# Revolution.net
KiCad netlist of a schematic drawn in Altium Designer
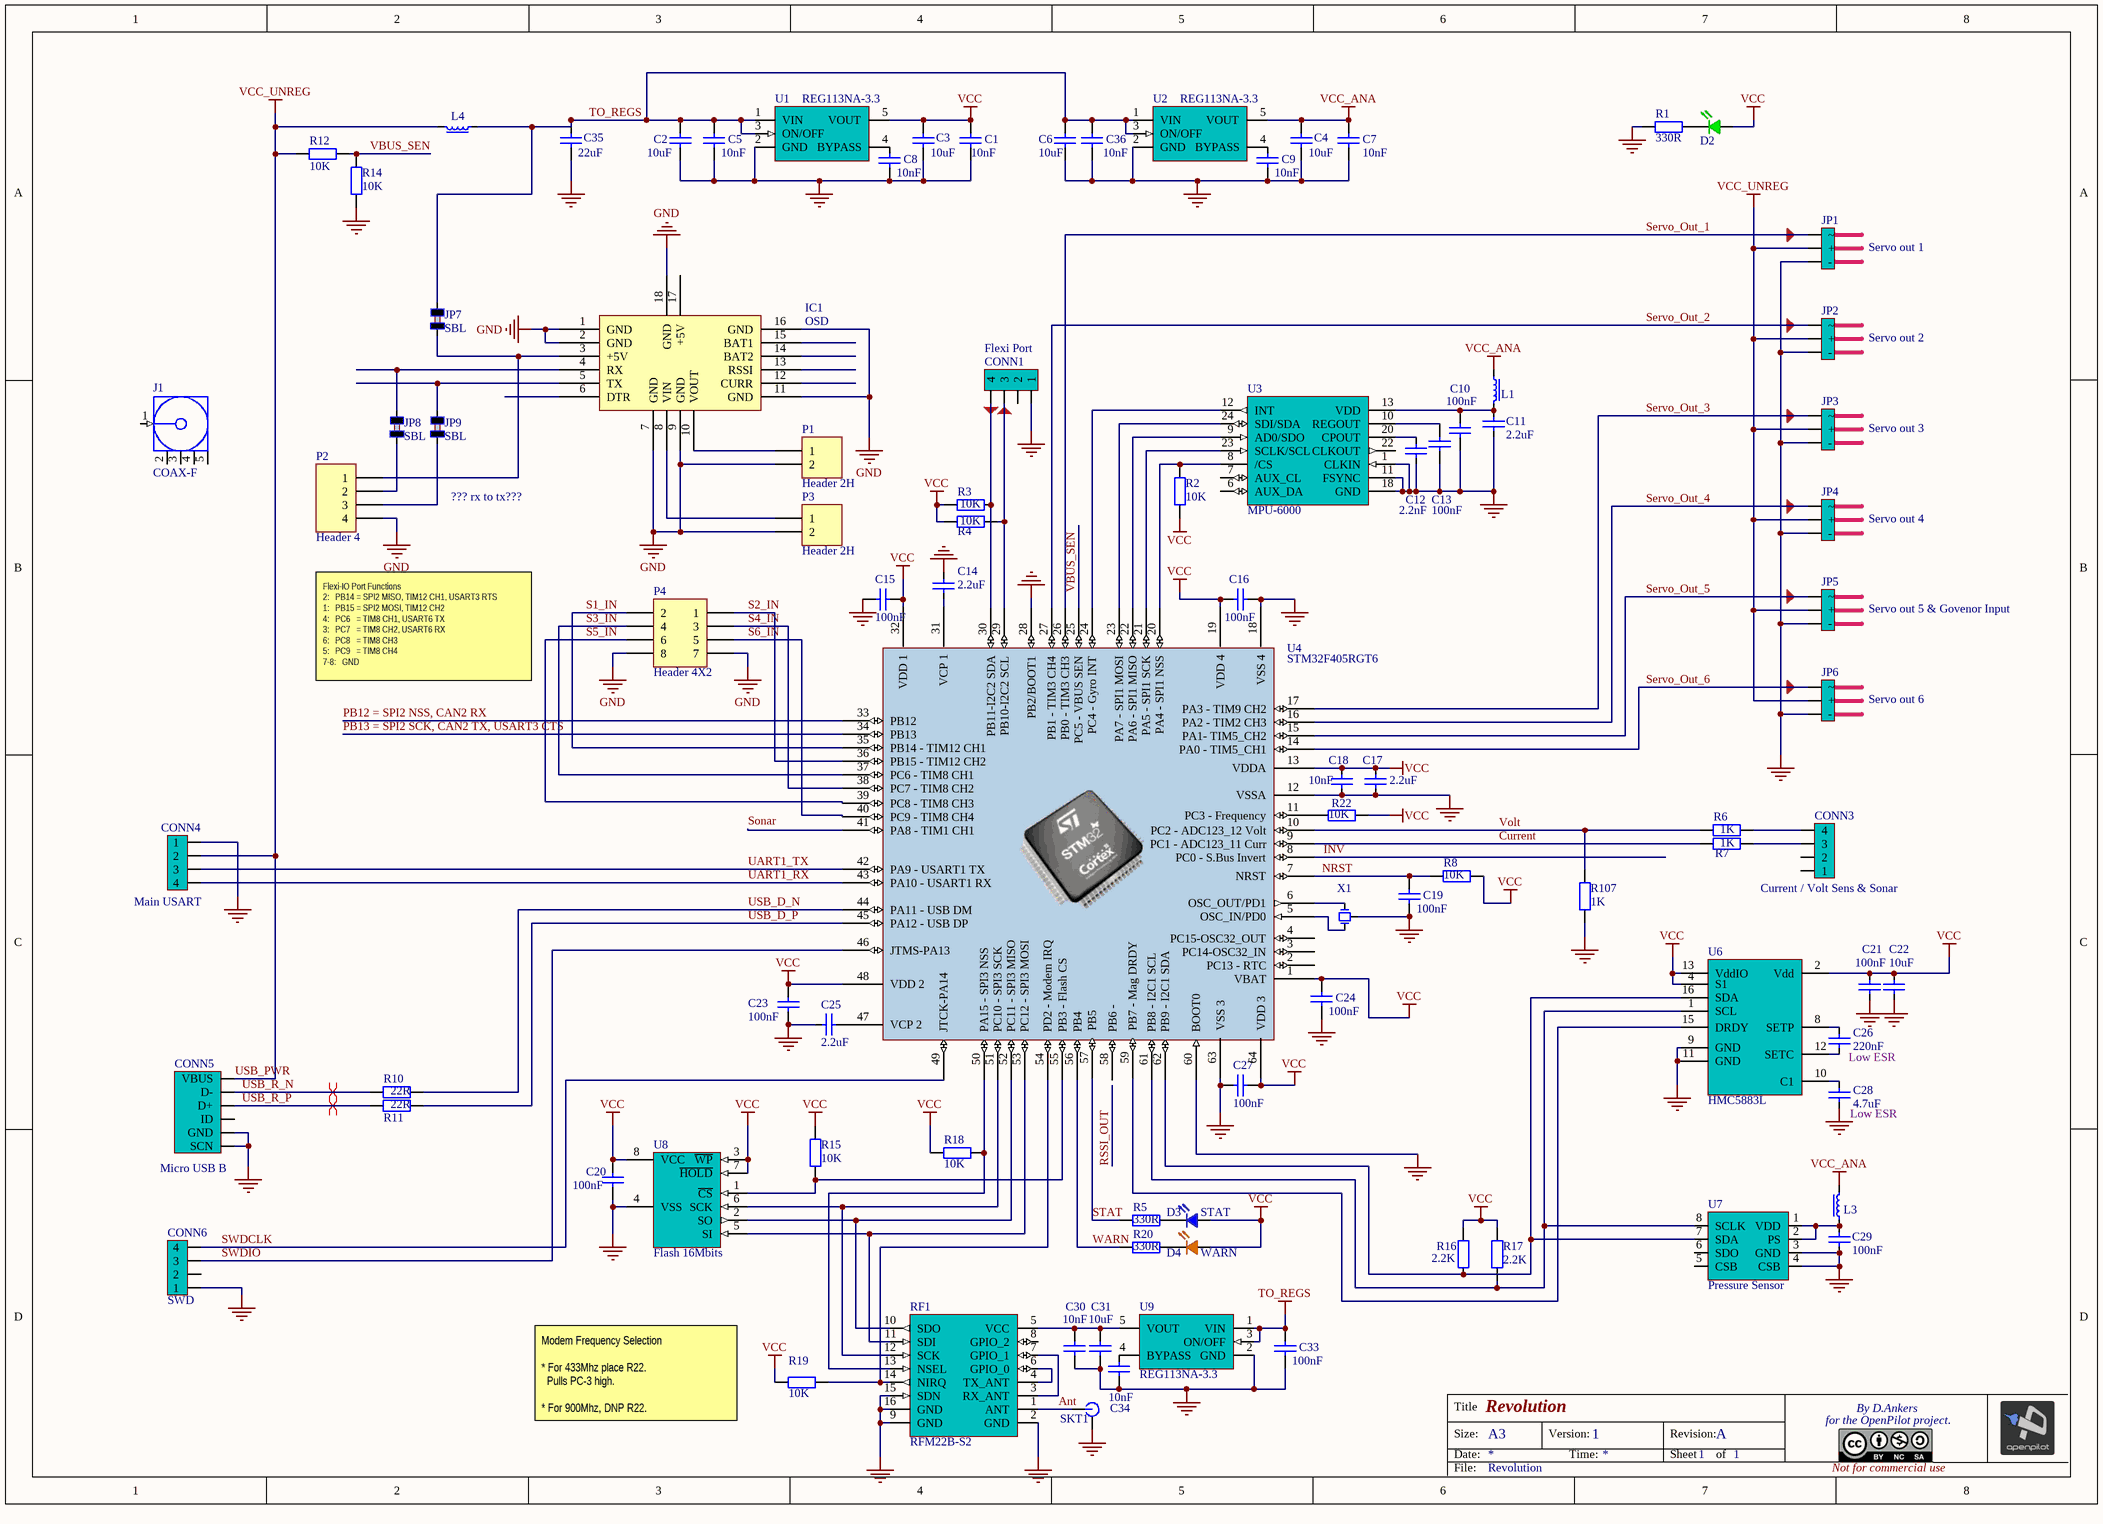
[diagram p0: Revolution.SchDoc]

(export (version "E")
  (design (tool "Eeschema 10.0.6"))
  (components
    (comp (ref "C1")
      (value "10nF")
      (footprint "CAP402N")
      (description "Capacitor SMD")
      (fields (field (name "Comment") "10n") (field (name "PUBLISHER") "The OpenPilot Project"))
      (libsource (lib "OpenPilot") (part "Cap402"))
    )
    (comp (ref "C2")
      (value "10uF")
      (footprint "CAP805L")
      (description "Capacitor SMD")
      (fields (field (name "Comment") "Cap805") (field (name "PUBLISHER") "The OpenPilot Project"))
      (libsource (lib "OpenPilot") (part "Cap805"))
    )
    (comp (ref "C3")
      (value "10uF")
      (footprint "CAP805L")
      (description "Capacitor SMD")
      (fields (field (name "Comment") "Cap805") (field (name "PUBLISHER") "The OpenPilot Project"))
      (libsource (lib "OpenPilot") (part "Cap805"))
    )
    (comp (ref "C4")
      (value "10uF")
      (footprint "CAP805L")
      (description "Capacitor SMD")
      (fields (field (name "Comment") "Cap805") (field (name "PUBLISHER") "The OpenPilot Project"))
      (libsource (lib "OpenPilot") (part "Cap805"))
    )
    (comp (ref "C5")
      (value "10nF")
      (footprint "CAP402N")
      (description "Capacitor SMD")
      (fields (field (name "Comment") "10n") (field (name "PUBLISHER") "The OpenPilot Project"))
      (libsource (lib "OpenPilot") (part "Cap402"))
    )
    (comp (ref "C6")
      (value "10uF")
      (footprint "CAP805L")
      (description "Capacitor SMD")
      (fields (field (name "Comment") "Cap805") (field (name "PUBLISHER") "The OpenPilot Project"))
      (libsource (lib "OpenPilot") (part "Cap805"))
    )
    (comp (ref "C7")
      (value "10nF")
      (footprint "CAP402N")
      (description "Capacitor SMD")
      (fields (field (name "Comment") "10n") (field (name "PUBLISHER") "The OpenPilot Project"))
      (libsource (lib "OpenPilot") (part "Cap402"))
    )
    (comp (ref "C8")
      (value "10nF")
      (footprint "CAP402N")
      (description "Capacitor SMD")
      (fields (field (name "Comment") "10n") (field (name "PUBLISHER") "The OpenPilot Project"))
      (libsource (lib "") (part "Cap402_2"))
    )
    (comp (ref "C9")
      (value "10nF")
      (footprint "CAP402N")
      (description "Capacitor SMD")
      (fields (field (name "Comment") "10n") (field (name "PUBLISHER") "The OpenPilot Project"))
      (libsource (lib "") (part "Cap402_2"))
    )
    (comp (ref "C10")
      (value "100nF")
      (footprint "CAP402N")
      (description "Capacitor SMD")
      (fields (field (name "Comment") "Cap402") (field (name "PUBLISHER") "The OpenPilot Project"))
      (libsource (lib "OpenPilot") (part "Cap402"))
    )
    (comp (ref "C11")
      (value "2.2uF")
      (footprint "CAP603L")
      (description "Capacitor SMD")
      (fields (field (name "Comment") "Cap603") (field (name "PUBLISHER") "The OpenPilot Project"))
      (libsource (lib "OpenPilot") (part "Cap603"))
    )
    (comp (ref "C12")
      (value "2.2nF")
      (footprint "CAP603L")
      (description "Capacitor SMD")
      (fields (field (name "Comment") "Cap603") (field (name "PUBLISHER") "The OpenPilot Project"))
      (libsource (lib "OpenPilot") (part "Cap603"))
    )
    (comp (ref "C13")
      (value "100nF")
      (footprint "CAP402N")
      (description "Capacitor SMD")
      (fields (field (name "Comment") "Cap402") (field (name "PUBLISHER") "The OpenPilot Project"))
      (libsource (lib "OpenPilot") (part "Cap402"))
    )
    (comp (ref "C14")
      (value "2.2uF")
      (footprint "CAP603L")
      (description "Capacitor SMD")
      (fields (field (name "Comment") "Cap603") (field (name "PUBLISHER") "The OpenPilot Project"))
      (libsource (lib "OpenPilot") (part "Cap603"))
    )
    (comp (ref "C15")
      (value "100nF")
      (footprint "CAP402N")
      (description "Capacitor SMD")
      (fields (field (name "Comment") "Cap402") (field (name "PUBLISHER") "The OpenPilot Project"))
      (libsource (lib "OpenPilot") (part "Cap402"))
    )
    (comp (ref "C16")
      (value "100nF")
      (footprint "CAP402N")
      (description "Capacitor SMD")
      (fields (field (name "Comment") "Cap402") (field (name "PUBLISHER") "The OpenPilot Project"))
      (libsource (lib "OpenPilot") (part "Cap402"))
    )
    (comp (ref "C17")
      (value "2.2uF")
      (footprint "CAP603L")
      (description "Capacitor SMD")
      (fields (field (name "Comment") "Cap603") (field (name "PUBLISHER") "The OpenPilot Project"))
      (libsource (lib "OpenPilot") (part "Cap603"))
    )
    (comp (ref "C18")
      (value "10nF")
      (footprint "CAP402N")
      (description "Capacitor SMD")
      (fields (field (name "Comment") "10n") (field (name "PUBLISHER") "The OpenPilot Project"))
      (libsource (lib "") (part "Cap402_1"))
    )
    (comp (ref "C19")
      (value "100nF")
      (footprint "CAP402N")
      (description "Capacitor SMD")
      (fields (field (name "Comment") "Cap402") (field (name "PUBLISHER") "The OpenPilot Project"))
      (libsource (lib "OpenPilot") (part "Cap402"))
    )
    (comp (ref "C20")
      (value "100nF")
      (footprint "CAP402N")
      (description "Capacitor SMD")
      (fields (field (name "Comment") "Cap402") (field (name "PUBLISHER") "The OpenPilot Project"))
      (libsource (lib "OpenPilot") (part "Cap402"))
    )
    (comp (ref "C21")
      (value "100nF")
      (footprint "CAP402N")
      (description "Capacitor SMD")
      (fields (field (name "Comment") "Cap402") (field (name "PUBLISHER") "The OpenPilot Project"))
      (libsource (lib "") (part "Cap402_1"))
    )
    (comp (ref "C22")
      (value "10uF")
      (footprint "CAP805L")
      (description "Capacitor SMD")
      (fields (field (name "Comment") "Cap805") (field (name "PUBLISHER") "The OpenPilot Project"))
      (libsource (lib "") (part "Cap805_1"))
    )
    (comp (ref "C23")
      (value "100nF")
      (footprint "CAP402N")
      (description "Capacitor SMD")
      (fields (field (name "Comment") "Cap402") (field (name "PUBLISHER") "The OpenPilot Project"))
      (libsource (lib "OpenPilot") (part "Cap402"))
    )
    (comp (ref "C24")
      (value "100nF")
      (footprint "CAP402N")
      (description "Capacitor SMD")
      (fields (field (name "Comment") "Cap402") (field (name "PUBLISHER") "The OpenPilot Project"))
      (libsource (lib "OpenPilot") (part "Cap402"))
    )
    (comp (ref "C25")
      (value "2.2uF")
      (footprint "CAP603L")
      (description "Capacitor SMD")
      (fields (field (name "Comment") "Cap603") (field (name "PUBLISHER") "The OpenPilot Project"))
      (libsource (lib "OpenPilot") (part "Cap603"))
    )
    (comp (ref "C26")
      (value "220nF")
      (footprint "CAP603L")
      (description "Capacitor SMD")
      (fields (field (name "Comment") "Cap603") (field (name "PUBLISHER") "The OpenPilot Project"))
      (libsource (lib "OpenPilot") (part "Cap603"))
    )
    (comp (ref "C27")
      (value "100nF")
      (footprint "CAP402N")
      (description "Capacitor SMD")
      (fields (field (name "Comment") "Cap402") (field (name "PUBLISHER") "The OpenPilot Project"))
      (libsource (lib "OpenPilot") (part "Cap402"))
    )
    (comp (ref "C28")
      (value "4.7uF")
      (footprint "CAP603L")
      (description "Capacitor SMD")
      (fields (field (name "Comment") "Cap603") (field (name "PUBLISHER") "The OpenPilot Project"))
      (libsource (lib "OpenPilot") (part "Cap603"))
    )
    (comp (ref "C29")
      (value "100nF")
      (footprint "CAP402N")
      (description "Capacitor SMD")
      (fields (field (name "Comment") "Cap402") (field (name "PUBLISHER") "The OpenPilot Project"))
      (libsource (lib "") (part "Cap402_1"))
    )
    (comp (ref "C30")
      (value "10nF")
      (footprint "CAP402N")
      (description "Capacitor SMD")
      (fields (field (name "Comment") "10n") (field (name "PUBLISHER") "The OpenPilot Project"))
      (libsource (lib "OpenPilot") (part "Cap402"))
    )
    (comp (ref "C31")
      (value "10uF")
      (footprint "CAP805L")
      (description "Capacitor SMD")
      (fields (field (name "Comment") "Cap805") (field (name "PUBLISHER") "The OpenPilot Project"))
      (libsource (lib "OpenPilot") (part "Cap805"))
    )
    (comp (ref "C33")
      (value "100nF")
      (footprint "CAP402N")
      (description "Capacitor SMD")
      (fields (field (name "Comment") "Cap402") (field (name "PUBLISHER") "The OpenPilot Project"))
      (libsource (lib "OpenPilot") (part "Cap402"))
    )
    (comp (ref "C34")
      (value "10nF")
      (footprint "CAP402N")
      (description "Capacitor SMD")
      (fields (field (name "Comment") "10n") (field (name "PUBLISHER") "The OpenPilot Project"))
      (libsource (lib "") (part "Cap402_2"))
    )
    (comp (ref "C35")
      (value "22uF")
      (footprint "CAP805L")
      (description "Capacitor SMD")
      (fields (field (name "Comment") "Cap805") (field (name "PUBLISHER") "The OpenPilot Project"))
      (libsource (lib "OpenPilot") (part "Cap805"))
    )
    (comp (ref "C36")
      (value "10nF")
      (footprint "CAP402N")
      (description "Capacitor SMD")
      (fields (field (name "Comment") "10n") (field (name "PUBLISHER") "The OpenPilot Project"))
      (libsource (lib "OpenPilot") (part "Cap402"))
    )
    (comp (ref "CONN1")
      (value "Flexi Port")
      (footprint "JST SH 4 Pin Side Entry")
      (description "JST-SH 4-pin Side Entry Socket")
      (fields (field (name "MANUFACTURER") "Generic Components"))
      (libsource (lib "") (part "JST-SH 4-pin Side Entry Socket_3"))
    )
    (comp (ref "CONN3")
      (value "Current / Volt Sens & Sonar")
      (footprint "JST SH 4 Pin Side Entry")
      (description "JST-SH 4-pin Side Entry Socket")
      (fields (field (name "MANUFACTURER") "Generic Components"))
      (libsource (lib "") (part "JST-SH 4-pin Side Entry Socket_2"))
    )
    (comp (ref "CONN4")
      (value "Main USART")
      (footprint "JST SH 4 Pin Side Entry")
      (description "JST-SH 4-pin Side Entry Socket")
      (fields (field (name "MANUFACTURER") "Generic Components"))
      (libsource (lib "OpenPilot") (part "JST-SH 4-pin Side Entry Socket"))
    )
    (comp (ref "CONN5")
      (value "Micro USB B")
      (footprint "Micro_USB")
      (description "USB Micro B SMT Socket")
      (fields (field (name "PUBLISHER") "The OpenPilot Project"))
      (libsource (lib "OpenPilot") (part "USB Micro B SMT"))
    )
    (comp (ref "CONN6")
      (value "SWD")
      (footprint "JST SH 4 Pin Side Entry")
      (description "JST-SH 4-pin Side Entry Socket")
      (fields (field (name "MANUFACTURER") "Generic Components"))
      (libsource (lib "") (part "JST-SH 4-pin Side Entry Socket_1"))
    )
    (comp (ref "D2")
      (value "Green")
      (footprint "LED603N")
      (description "Green 603 LED")
      (libsource (lib "OpenPilot") (part "LED 603 Gr"))
    )
    (comp (ref "D3")
      (value "STAT")
      (footprint "LED603N")
      (description "Blue 603 LED")
      (libsource (lib "OpenPilot") (part "LED 603 Bl"))
    )
    (comp (ref "D4")
      (value "WARN")
      (footprint "LED603N")
      (description "Orange 603 LED")
      (libsource (lib "OpenPilot") (part "LED 603 Or"))
    )
    (comp (ref "IC1") (value "OSD") (footprint "OSD") (libsource (lib "Schlib1") (part "OSD")))
    (comp (ref "J1")
      (value "COAX-F")
      (footprint "MCX5.08-H5")
      (fields (field (name "PUBLISHER") "Altium Limited"))
      (libsource (lib "Miscellaneous Connectors") (part "COAX-F"))
    )
    (comp (ref "JP1")
      (value "Servo out 1")
      (footprint "SIP3 - 0.1")
      (description "Header, 3-Pin, 0.1\"")
      (fields (field (name "MANUFACTURER") "Generic Components"))
      (libsource (lib "OpenPilot") (part "Hdr 3 Pin 0.1"))
    )
    (comp (ref "JP2")
      (value "Servo out 2")
      (footprint "SIP3 - 0.1")
      (description "Header, 3-Pin, 0.1\"")
      (fields (field (name "MANUFACTURER") "Generic Components"))
      (libsource (lib "OpenPilot") (part "Hdr 3 Pin 0.1"))
    )
    (comp (ref "JP3")
      (value "Servo out 3")
      (footprint "SIP3 - 0.1")
      (description "Header, 3-Pin, 0.1\"")
      (fields (field (name "MANUFACTURER") "Generic Components"))
      (libsource (lib "OpenPilot") (part "Hdr 3 Pin 0.1"))
    )
    (comp (ref "JP4")
      (value "Servo out 4")
      (footprint "SIP3 - 0.1")
      (description "Header, 3-Pin, 0.1\"")
      (fields (field (name "MANUFACTURER") "Generic Components"))
      (libsource (lib "OpenPilot") (part "Hdr 3 Pin 0.1"))
    )
    (comp (ref "JP5")
      (value "Servo out 5 & Govenor Input")
      (footprint "SIP3 - 0.1")
      (description "Header, 3-Pin, 0.1\"")
      (fields (field (name "MANUFACTURER") "Generic Components"))
      (libsource (lib "OpenPilot") (part "Hdr 3 Pin 0.1"))
    )
    (comp (ref "JP6")
      (value "Servo out 6")
      (footprint "SIP3 - 0.1")
      (description "Header, 3-Pin, 0.1\"")
      (fields (field (name "MANUFACTURER") "Generic Components"))
      (libsource (lib "OpenPilot") (part "Hdr 3 Pin 0.1"))
    )
    (comp (ref "JP7")
      (value "SBL")
      (footprint "TOUCH JMP 2PAD")
      (description "2 Pad Touch Jumper")
      (fields (field (name "PUBLISHER") "The OpenPilot Project"))
      (libsource (lib "OpenPilot") (part "2 PAD Touch JMP"))
    )
    (comp (ref "JP8")
      (value "SBL")
      (footprint "TOUCH JMP 2PAD")
      (description "2 Pad Touch Jumper")
      (fields (field (name "PUBLISHER") "The OpenPilot Project"))
      (libsource (lib "OpenPilot") (part "2 PAD Touch JMP"))
    )
    (comp (ref "JP9")
      (value "SBL")
      (footprint "TOUCH JMP 2PAD")
      (description "2 Pad Touch Jumper")
      (fields (field (name "PUBLISHER") "The OpenPilot Project"))
      (libsource (lib "OpenPilot") (part "2 PAD Touch JMP"))
    )
    (comp (ref "L1")
      (value "FB 300mA")
      (footprint "IND603N")
      (description "Ferrite Bead 300mA")
      (fields
        (field (name "MANUFACTURER") "Generic Components")
        (field (name "PUBLISHER") "The OpenPilot Project")
      )
      (libsource (lib "OpenPilot") (part "FerriteBead 300mA"))
    )
    (comp (ref "L3")
      (value "FB 300mA")
      (footprint "IND603N")
      (description "Ferrite Bead 300mA")
      (fields
        (field (name "MANUFACTURER") "Generic Components")
        (field (name "PUBLISHER") "The OpenPilot Project")
      )
      (libsource (lib "OpenPilot") (part "FerriteBead 300mA"))
    )
    (comp (ref "L4")
      (value "FB 300mA")
      (footprint "IND603N")
      (description "Ferrite Bead 300mA")
      (fields
        (field (name "MANUFACTURER") "Generic Components")
        (field (name "PUBLISHER") "The OpenPilot Project")
      )
      (libsource (lib "OpenPilot") (part "FerriteBead 300mA"))
    )
    (comp (ref "P1")
      (value "Header 2H")
      (footprint "HDR1X2H")
      (description "Header, 2-Pin, Right Angle")
      (fields (field (name "PUBLISHER") "Altium Limited"))
      (libsource (lib "Miscellaneous Connectors") (part "Header 2H"))
    )
    (comp (ref "P2")
      (value "Header 4")
      (footprint "HDR1X4")
      (description "Header, 4-Pin")
      (fields (field (name "PUBLISHER") "Altium Limited"))
      (libsource (lib "Miscellaneous Connectors") (part "Header 4"))
    )
    (comp (ref "P3")
      (value "Header 2H")
      (footprint "HDR1X2H")
      (description "Header, 2-Pin, Right Angle")
      (fields (field (name "PUBLISHER") "Altium Limited"))
      (libsource (lib "Miscellaneous Connectors") (part "Header 2H"))
    )
    (comp (ref "P4")
      (value "Header 4X2")
      (footprint "HDR2X4")
      (description "Header, 4-Pin, Dual row")
      (fields (field (name "PUBLISHER") "Altium Limited"))
      (libsource (lib "Miscellaneous Connectors") (part "Header 4X2"))
    )
    (comp (ref "R1")
      (value "330R")
      (footprint "RES402N")
      (description "Resistor SMD")
      (fields (field (name "Comment") "Res402") (field (name "PUBLISHER") "The OpenPilot Project"))
      (libsource (lib "OpenPilot") (part "Res402"))
    )
    (comp (ref "R2")
      (value "10K")
      (footprint "RES402N")
      (description "Resistor SMD")
      (fields (field (name "Comment") "Res402") (field (name "PUBLISHER") "The OpenPilot Project"))
      (libsource (lib "") (part "Res402_1"))
    )
    (comp (ref "R3")
      (value "10K")
      (footprint "RES402N")
      (description "Resistor SMD")
      (fields (field (name "Comment") "Res402") (field (name "PUBLISHER") "The OpenPilot Project"))
      (libsource (lib "") (part "Res402_3"))
    )
    (comp (ref "R4")
      (value "10K")
      (footprint "RES402N")
      (description "Resistor SMD")
      (fields (field (name "Comment") "Res402") (field (name "PUBLISHER") "The OpenPilot Project"))
      (libsource (lib "") (part "Res402_2"))
    )
    (comp (ref "R5")
      (value "330R")
      (footprint "RES402N")
      (description "Resistor SMD")
      (fields (field (name "Comment") "Res402") (field (name "PUBLISHER") "The OpenPilot Project"))
      (libsource (lib "") (part "Res402_2"))
    )
    (comp (ref "R6")
      (value "1K")
      (footprint "RES402N")
      (description "Resistor SMD")
      (fields (field (name "Comment") "Res402") (field (name "PUBLISHER") "The OpenPilot Project"))
      (libsource (lib "OpenPilot") (part "Res402"))
    )
    (comp (ref "R7")
      (value "1K")
      (footprint "RES402N")
      (description "Resistor SMD")
      (fields (field (name "Comment") "Res402") (field (name "PUBLISHER") "The OpenPilot Project"))
      (libsource (lib "OpenPilot") (part "Res402"))
    )
    (comp (ref "R8")
      (value "10K")
      (footprint "RES402N")
      (description "Resistor SMD")
      (fields (field (name "Comment") "Res402") (field (name "PUBLISHER") "The OpenPilot Project"))
      (libsource (lib "OpenPilot") (part "Res402"))
    )
    (comp (ref "R10")
      (value "22R")
      (footprint "RES402N")
      (description "Resistor SMD")
      (fields (field (name "Comment") "Res402") (field (name "PUBLISHER") "The OpenPilot Project"))
      (libsource (lib "") (part "Res402_2"))
    )
    (comp (ref "R11")
      (value "22R")
      (footprint "RES402N")
      (description "Resistor SMD")
      (fields (field (name "Comment") "Res402") (field (name "PUBLISHER") "The OpenPilot Project"))
      (libsource (lib "") (part "Res402_2"))
    )
    (comp (ref "R12")
      (value "10K")
      (footprint "RES402N")
      (description "Resistor SMD")
      (fields (field (name "Comment") "Res402") (field (name "PUBLISHER") "The OpenPilot Project"))
      (libsource (lib "OpenPilot") (part "Res402"))
    )
    (comp (ref "R14")
      (value "10K")
      (footprint "RES402N")
      (description "Resistor SMD")
      (fields (field (name "Comment") "Res402") (field (name "PUBLISHER") "The OpenPilot Project"))
      (libsource (lib "") (part "Res402_1"))
    )
    (comp (ref "R15")
      (value "10K")
      (footprint "RES402N")
      (description "Resistor SMD")
      (fields (field (name "Comment") "Res402") (field (name "PUBLISHER") "The OpenPilot Project"))
      (libsource (lib "") (part "Res402_5"))
    )
    (comp (ref "R16")
      (value "2.2K")
      (footprint "RES402N")
      (description "Resistor SMD")
      (fields (field (name "Comment") "Res402") (field (name "PUBLISHER") "The OpenPilot Project"))
      (libsource (lib "") (part "Res402_4"))
    )
    (comp (ref "R17")
      (value "2.2K")
      (footprint "RES402N")
      (description "Resistor SMD")
      (fields (field (name "Comment") "Res402") (field (name "PUBLISHER") "The OpenPilot Project"))
      (libsource (lib "") (part "Res402_5"))
    )
    (comp (ref "R18")
      (value "10K")
      (footprint "RES402N")
      (description "Resistor SMD")
      (fields (field (name "Comment") "Res402") (field (name "PUBLISHER") "The OpenPilot Project"))
      (libsource (lib "OpenPilot") (part "Res402"))
    )
    (comp (ref "R19")
      (value "10K")
      (footprint "RES402N")
      (description "Resistor SMD")
      (fields (field (name "Comment") "Res402") (field (name "PUBLISHER") "The OpenPilot Project"))
      (libsource (lib "") (part "Res402_2"))
    )
    (comp (ref "R20")
      (value "330R")
      (footprint "RES402N")
      (description "Resistor SMD")
      (fields (field (name "Comment") "Res402") (field (name "PUBLISHER") "The OpenPilot Project"))
      (libsource (lib "") (part "Res402_2"))
    )
    (comp (ref "R22")
      (value "10K")
      (footprint "RES402N")
      (description "Resistor SMD")
      (fields (field (name "Comment") "Res402") (field (name "PUBLISHER") "The OpenPilot Project"))
      (libsource (lib "") (part "Res402_2"))
    )
    (comp (ref "R107")
      (value "1K")
      (footprint "RES402N")
      (description "Resistor SMD")
      (fields (field (name "Comment") "Res402") (field (name "PUBLISHER") "The OpenPilot Project"))
      (libsource (lib "") (part "Res402_1"))
    )
    (comp (ref "RF1")
      (value "RFM22B-S2")
      (footprint "RFM22-S2")
      (description "UHF 100mW Transceiver")
      (libsource (lib "OpenPilot") (part "RFM22B-S2"))
    )
    (comp (ref "SKT1")
      (value "MMCX Thru hole")
      (footprint "MMCX_SOCKET")
      (description "MMCX Socket")
      (libsource (lib "OpenPilot") (part "MMCX Thru hole"))
    )
    (comp (ref "U1")
      (value "REG113NA-3.3")
      (footprint "SOT23-5L")
      (description "3.3V 400mA LDO Regulator")
      (libsource (lib "OpenPilot") (part "REG113NA-3.3"))
    )
    (comp (ref "U2")
      (value "REG113NA-3.3")
      (footprint "SOT23-5L")
      (description "3.3V 400mA LDO Regulator")
      (libsource (lib "OpenPilot") (part "REG113NA-3.3"))
    )
    (comp (ref "U3")
      (value "MPU-6000")
      (footprint "IMU-3000")
      (description "Invensense MPU-3/6000,  3-axis Gyros & Accel on 6000")
      (fields (field (name "MANUFACTURER") "Invensense") (field (name "PUBLISHER") "The OpenPilot Project"))
      (libsource (lib "OpenPilot") (part "MPU-3/6000"))
    )
    (comp (ref "U4")
      (value "STM32F405RGT6")
      (footprint "STM32 64 Lead")
      (description "STM32 ARM-based 32-bit MCU with 1MB Flash, 64-pin LQFP, Industrial Temperature")
      (libsource (lib "OpenPilot") (part "STM32F103RET6"))
    )
    (comp (ref "U6")
      (value "HMC5883L")
      (footprint "LPCC-16")
      (description "IC, Magnetometer, 3 axis, +/- 8 Oe, I2C, 160Hz")
      (fields (field (name "MANUFACTURER") "Honeywell") (field (name "PUBLISHER") "The OpenPilot Project"))
      (libsource (lib "OpenPilot") (part "HMC5883L"))
    )
    (comp (ref "U7")
      (value "Pressure Sensor")
      (footprint "MS5611-01BA03")
      (description "Pressure Sensor - MS5611-01BA03")
      (libsource (lib "OpenPilot") (part "MS5611-01BA03"))
    )
    (comp (ref "U8")
      (value "Flash 16Mbits")
      (footprint "SOIC8_N")
      (description "16Mbit SPI Flash Memory")
      (fields (field (name "PUBLISHER") "The OpenPilot Project"))
      (libsource (lib "OpenPilot") (part "Flash 16Mb 75MHZ 8SOIC"))
    )
    (comp (ref "U9")
      (value "REG113NA-3.3")
      (footprint "SOT23-5L")
      (description "3.3V 400mA LDO Regulator")
      (libsource (lib "") (part "REG113NA-3.3_1"))
    )
    (comp (ref "X1")
      (value "8Mhz Ceralock")
      (footprint "CERALOCK 8Mhz")
      (description "Ceralock 8Mhz with caps")
      (fields (field (name "PUBLISHER") "The OpenPilot Project"))
      (libsource (lib "OpenPilot") (part "CERALOCK8"))
    )
  )
  (nets
    (net (code "1") (name "/Ant") (class "Default")
      (node (ref "RF1") (pin "1") (pinfunction "ANT_1") (pintype "passive"))
      (node (ref "SKT1") (pin "1") (pinfunction "PIN_1") (pintype "passive"))
    )
    (net (code "2") (name "/Current") (class "Default")
      (node (ref "R7") (pin "1") (pinfunction "1_1") (pintype "passive"))
      (node (ref "U4") (pin "9") (pinfunction "PC1_-_ADC123_11_Curr_9") (pintype "bidirectional"))
    )
    (net (code "3") (name "/INV") (class "Default")
      (node (ref "U4") (pin "8") (pinfunction "PC0_-_S.Bus_Invert_8") (pintype "bidirectional"))
    )
    (net (code "4") (name "/NRST") (class "Default")
      (node (ref "C19") (pin "2") (pinfunction "2_2") (pintype "passive"))
      (node (ref "R8") (pin "1") (pinfunction "1_1") (pintype "passive"))
      (node (ref "U4") (pin "7") (pinfunction "NRST_7") (pintype "bidirectional"))
    )
    (net (code "5") (name "/PB12 = SPI2 NSS, CAN2 RX") (class "Default")
      (node (ref "U4") (pin "33") (pinfunction "PB12_33") (pintype "bidirectional"))
    )
    (net (code "6") (name "/PB13 = SPI2 SCK, CAN2 TX, USART3 CTS") (class "Default")
      (node (ref "U4") (pin "34") (pinfunction "PB13_34") (pintype "bidirectional"))
    )
    (net (code "8") (name "/S1_IN") (class "Default")
      (node (ref "P4") (pin "2") (pinfunction "2_2") (pintype "passive"))
      (node (ref "U4") (pin "35") (pinfunction "PB14_-_TIM12_CH1_35") (pintype "bidirectional"))
    )
    (net (code "9") (name "/S2_IN") (class "Default")
      (node (ref "P4") (pin "1") (pinfunction "1_1") (pintype "passive"))
      (node (ref "U4") (pin "36") (pinfunction "PB15_-_TIM12_CH2_36") (pintype "bidirectional"))
    )
    (net (code "10") (name "/S3_IN") (class "Default")
      (node (ref "P4") (pin "4") (pinfunction "4_4") (pintype "passive"))
      (node (ref "U4") (pin "37") (pinfunction "PC6_-_TIM8_CH1_37") (pintype "bidirectional"))
    )
    (net (code "11") (name "/S4_IN") (class "Default")
      (node (ref "P4") (pin "3") (pinfunction "3_3") (pintype "passive"))
      (node (ref "U4") (pin "38") (pinfunction "PC7_-_TIM8_CH2_38") (pintype "bidirectional"))
    )
    (net (code "12") (name "/S5_IN") (class "Default")
      (node (ref "P4") (pin "6") (pinfunction "6_6") (pintype "passive"))
      (node (ref "U4") (pin "39") (pinfunction "PC8_-_TIM8_CH3_39") (pintype "bidirectional"))
    )
    (net (code "13") (name "/S6_IN") (class "Default")
      (node (ref "P4") (pin "5") (pinfunction "5_5") (pintype "passive"))
      (node (ref "U4") (pin "40") (pinfunction "PC9_-_TIM8_CH4_40") (pintype "bidirectional"))
    )
    (net (code "14") (name "/STAT") (class "Default")
      (node (ref "R5") (pin "2") (pinfunction "2_2") (pintype "passive"))
      (node (ref "U4") (pin "57") (pinfunction "PB5_57") (pintype "bidirectional"))
    )
    (net (code "15") (name "/SWDCLK") (class "Default")
      (node (ref "CONN6") (pin "4") (pinfunction "4_4") (pintype "passive"))
      (node (ref "U4") (pin "49") (pinfunction "JTCK-PA14_49") (pintype "bidirectional"))
    )
    (net (code "16") (name "/SWDIO") (class "Default")
      (node (ref "CONN6") (pin "3") (pinfunction "3_3") (pintype "passive"))
      (node (ref "U4") (pin "46") (pinfunction "JTMS-PA13_46") (pintype "bidirectional"))
    )
    (net (code "17") (name "/Servo_Out_1") (class "Default")
      (node (ref "JP1") (pin "1") (pinfunction "~_1") (pintype "passive"))
      (node (ref "U4") (pin "26") (pinfunction "PB0_-_TIM3_CH3_26") (pintype "bidirectional"))
    )
    (net (code "18") (name "/Servo_Out_2") (class "Default")
      (node (ref "JP2") (pin "1") (pinfunction "~_1") (pintype "passive"))
      (node (ref "U4") (pin "27") (pinfunction "PB1_-_TIM3_CH4_27") (pintype "bidirectional"))
    )
    (net (code "19") (name "/Servo_Out_3") (class "Default")
      (node (ref "JP3") (pin "1") (pinfunction "~_1") (pintype "passive"))
      (node (ref "U4") (pin "17") (pinfunction "PA3_-_TIM9_CH2_17") (pintype "bidirectional"))
    )
    (net (code "20") (name "/Servo_Out_4") (class "Default")
      (node (ref "JP4") (pin "1") (pinfunction "~_1") (pintype "passive"))
      (node (ref "U4") (pin "16") (pinfunction "PA2_-_TIM2_CH3_16") (pintype "bidirectional"))
    )
    (net (code "21") (name "/Servo_Out_5") (class "Default")
      (node (ref "JP5") (pin "1") (pinfunction "~_1") (pintype "passive"))
      (node (ref "U4") (pin "15") (pinfunction "PA1-_TIM5_CH2_15") (pintype "bidirectional"))
    )
    (net (code "22") (name "/Servo_Out_6") (class "Default")
      (node (ref "JP6") (pin "1") (pinfunction "~_1") (pintype "passive"))
      (node (ref "U4") (pin "14") (pinfunction "PA0_-_TIM5_CH1_14") (pintype "bidirectional"))
    )
    (net (code "23") (name "/Sonar") (class "Default")
      (node (ref "U4") (pin "41") (pinfunction "PA8_-_TIM1_CH1_41") (pintype "bidirectional"))
    )
    (net (code "24") (name "/UART1_RX") (class "Default")
      (node (ref "CONN4") (pin "4") (pinfunction "4_4") (pintype "passive"))
      (node (ref "U4") (pin "43") (pinfunction "PA10_-_USART1_RX_43") (pintype "bidirectional"))
    )
    (net (code "25") (name "/UART1_TX") (class "Default")
      (node (ref "CONN4") (pin "3") (pinfunction "3_3") (pintype "passive"))
      (node (ref "U4") (pin "42") (pinfunction "PA9_-_USART1_TX_42") (pintype "bidirectional"))
    )
    (net (code "26") (name "/USB_D_N") (class "Default")
      (node (ref "R10") (pin "1") (pinfunction "1_1") (pintype "passive"))
      (node (ref "U4") (pin "44") (pinfunction "PA11_-_USB_DM_44") (pintype "bidirectional"))
    )
    (net (code "27") (name "/USB_D_P") (class "Default")
      (node (ref "R11") (pin "1") (pinfunction "1_1") (pintype "passive"))
      (node (ref "U4") (pin "45") (pinfunction "PA12_-_USB_DP_45") (pintype "bidirectional"))
    )
    (net (code "28") (name "/USB_R_N") (class "Default")
      (node (ref "CONN5") (pin "2") (pinfunction "D-_2") (pintype "passive"))
      (node (ref "R10") (pin "2") (pinfunction "2_2") (pintype "passive"))
    )
    (net (code "29") (name "/USB_R_P") (class "Default")
      (node (ref "CONN5") (pin "3") (pinfunction "D+_3") (pintype "passive"))
      (node (ref "R11") (pin "2") (pinfunction "2_2") (pintype "passive"))
    )
    (net (code "30") (name "/VBUS_SEN") (class "Default")
      (node (ref "R12") (pin "2") (pinfunction "2_2") (pintype "passive"))
      (node (ref "R14") (pin "2") (pinfunction "2_2") (pintype "passive"))
      (node (ref "U4") (pin "25") (pinfunction "PC5_-_VBUS_SEN_25") (pintype "bidirectional"))
    )
    (net (code "31") (name "/Volt") (class "Default")
      (node (ref "R107") (pin "2") (pinfunction "2_2") (pintype "passive"))
      (node (ref "R6") (pin "1") (pinfunction "1_1") (pintype "passive"))
      (node (ref "U4") (pin "10") (pinfunction "PC2_-_ADC123_12_Volt_10") (pintype "bidirectional"))
    )
    (net (code "32") (name "/WARN") (class "Default")
      (node (ref "R20") (pin "2") (pinfunction "2_2") (pintype "passive"))
      (node (ref "U4") (pin "56") (pinfunction "PB4_56") (pintype "bidirectional"))
    )
    (net (code "33") (name "GND") (class "Default")
      (node (ref "C1") (pin "2") (pinfunction "2_2") (pintype "passive"))
      (node (ref "C10") (pin "1") (pinfunction "1_1") (pintype "passive"))
      (node (ref "C11") (pin "2") (pinfunction "2_2") (pintype "passive"))
      (node (ref "C12") (pin "1") (pinfunction "1_1") (pintype "passive"))
      (node (ref "C13") (pin "2") (pinfunction "2_2") (pintype "passive"))
      (node (ref "C14") (pin "1") (pinfunction "1_1") (pintype "passive"))
      (node (ref "C15") (pin "2") (pinfunction "2_2") (pintype "passive"))
      (node (ref "C16") (pin "1") (pinfunction "1_1") (pintype "passive"))
      (node (ref "C17") (pin "1") (pinfunction "1_1") (pintype "passive"))
      (node (ref "C18") (pin "2") (pinfunction "2_2") (pintype "passive"))
      (node (ref "C19") (pin "1") (pinfunction "1_1") (pintype "passive"))
      (node (ref "C2") (pin "2") (pinfunction "2_2") (pintype "passive"))
      (node (ref "C20") (pin "1") (pinfunction "1_1") (pintype "passive"))
      (node (ref "C21") (pin "2") (pinfunction "2_2") (pintype "passive"))
      (node (ref "C22") (pin "1") (pinfunction "1_1") (pintype "passive"))
      (node (ref "C23") (pin "2") (pinfunction "2_2") (pintype "passive"))
      (node (ref "C24") (pin "1") (pinfunction "1_1") (pintype "passive"))
      (node (ref "C25") (pin "1") (pinfunction "1_1") (pintype "passive"))
      (node (ref "C27") (pin "2") (pinfunction "2_2") (pintype "passive"))
      (node (ref "C28") (pin "2") (pinfunction "2_2") (pintype "passive"))
      (node (ref "C29") (pin "2") (pinfunction "2_2") (pintype "passive"))
      (node (ref "C3") (pin "2") (pinfunction "2_2") (pintype "passive"))
      (node (ref "C30") (pin "2") (pinfunction "2_2") (pintype "passive"))
      (node (ref "C31") (pin "2") (pinfunction "2_2") (pintype "passive"))
      (node (ref "C33") (pin "1") (pinfunction "1_1") (pintype "passive"))
      (node (ref "C34") (pin "2") (pinfunction "2_2") (pintype "passive"))
      (node (ref "C35") (pin "2") (pinfunction "2_2") (pintype "passive"))
      (node (ref "C36") (pin "2") (pinfunction "2_2") (pintype "passive"))
      (node (ref "C4") (pin "2") (pinfunction "2_2") (pintype "passive"))
      (node (ref "C5") (pin "2") (pinfunction "2_2") (pintype "passive"))
      (node (ref "C6") (pin "2") (pinfunction "2_2") (pintype "passive"))
      (node (ref "C7") (pin "2") (pinfunction "2_2") (pintype "passive"))
      (node (ref "C8") (pin "2") (pinfunction "2_2") (pintype "passive"))
      (node (ref "C9") (pin "2") (pinfunction "2_2") (pintype "passive"))
      (node (ref "CONN1") (pin "1") (pinfunction "1_1") (pintype "passive"))
      (node (ref "CONN4") (pin "1") (pinfunction "1_1") (pintype "passive"))
      (node (ref "CONN5") (pin "0") (pinfunction "SCN_0") (pintype "passive"))
      (node (ref "CONN5") (pin "5") (pinfunction "GND_5") (pintype "passive"))
      (node (ref "CONN6") (pin "1") (pinfunction "1_1") (pintype "passive"))
      (node (ref "IC1") (pin "1") (pinfunction "GND_1") (pintype "passive"))
      (node (ref "IC1") (pin "11") (pinfunction "GND_11") (pintype "passive"))
      (node (ref "IC1") (pin "16") (pinfunction "GND_16") (pintype "passive"))
      (node (ref "IC1") (pin "18") (pinfunction "GND_18") (pintype "passive"))
      (node (ref "IC1") (pin "2") (pinfunction "GND_2") (pintype "passive"))
      (node (ref "IC1") (pin "7") (pinfunction "GND_7") (pintype "passive"))
      (node (ref "IC1") (pin "9") (pinfunction "GND_9") (pintype "passive"))
      (node (ref "JP1") (pin "3") (pinfunction "-_3") (pintype "passive"))
      (node (ref "JP2") (pin "3") (pinfunction "-_3") (pintype "passive"))
      (node (ref "JP3") (pin "3") (pinfunction "-_3") (pintype "passive"))
      (node (ref "JP4") (pin "3") (pinfunction "-_3") (pintype "passive"))
      (node (ref "JP5") (pin "3") (pinfunction "-_3") (pintype "passive"))
      (node (ref "JP6") (pin "3") (pinfunction "-_3") (pintype "passive"))
      (node (ref "P1") (pin "2") (pinfunction "2_2") (pintype "passive"))
      (node (ref "P2") (pin "4") (pinfunction "4_4") (pintype "passive"))
      (node (ref "P3") (pin "2") (pinfunction "2_2") (pintype "passive"))
      (node (ref "P4") (pin "7") (pinfunction "7_7") (pintype "passive"))
      (node (ref "P4") (pin "8") (pinfunction "8_8") (pintype "passive"))
      (node (ref "R1") (pin "1") (pinfunction "1_1") (pintype "passive"))
      (node (ref "R107") (pin "1") (pinfunction "1_1") (pintype "passive"))
      (node (ref "R14") (pin "1") (pinfunction "1_1") (pintype "passive"))
      (node (ref "RF1") (pin "15") (pinfunction "SDN_15") (pintype "input"))
      (node (ref "RF1") (pin "16") (pinfunction "GND_16") (pintype "power_in"))
      (node (ref "RF1") (pin "2") (pinfunction "GND_2") (pintype "power_in"))
      (node (ref "RF1") (pin "9") (pinfunction "GND_9") (pintype "power_in"))
      (node (ref "SKT1") (pin "2") (pinfunction "GND_2") (pintype "passive"))
      (node (ref "U1") (pin "2") (pinfunction "GND_2") (pintype "power_in"))
      (node (ref "U2") (pin "2") (pinfunction "GND_2") (pintype "power_in"))
      (node (ref "U3") (pin "1") (pinfunction "CLKIN_1") (pintype "input"))
      (node (ref "U3") (pin "11") (pinfunction "FSYNC_11") (pintype "passive"))
      (node (ref "U3") (pin "18") (pinfunction "GND_18") (pintype "power_in"))
      (node (ref "U4") (pin "12") (pinfunction "VSSA_12") (pintype "power_in"))
      (node (ref "U4") (pin "18") (pinfunction "VSS_4_18") (pintype "power_in"))
      (node (ref "U4") (pin "28") (pinfunction "PB2/BOOT1_28") (pintype "bidirectional"))
      (node (ref "U4") (pin "60") (pinfunction "BOOT0_60") (pintype "input"))
      (node (ref "U4") (pin "63") (pinfunction "VSS_3_63") (pintype "power_in"))
      (node (ref "U6") (pin "11") (pinfunction "GND_11") (pintype "passive"))
      (node (ref "U6") (pin "9") (pinfunction "GND_9") (pintype "passive"))
      (node (ref "U7") (pin "3") (pinfunction "GND_3") (pintype "power_in"))
      (node (ref "U7") (pin "4") (pinfunction "CSB_4") (pintype "passive"))
      (node (ref "U8") (pin "4") (pinfunction "VSS_4") (pintype "power_in"))
      (node (ref "U9") (pin "2") (pinfunction "GND_2") (pintype "power_in"))
      (node (ref "X1") (pin "3") (pinfunction "3_3") (pintype "passive"))
    )
    (net (code "34") (name "Net-(CONN3-Pad3)") (class "Default")
      (node (ref "CONN3") (pin "3") (pinfunction "3_3") (pintype "passive"))
      (node (ref "R7") (pin "2") (pinfunction "2_2") (pintype "passive"))
    )
    (net (code "35") (name "Net-(CONN3-Pad4)") (class "Default")
      (node (ref "CONN3") (pin "4") (pinfunction "4_4") (pintype "passive"))
      (node (ref "R6") (pin "2") (pinfunction "2_2") (pintype "passive"))
    )
    (net (code "36") (name "Net-(D2-K)") (class "Default")
      (node (ref "D2") (pin "1") (pinfunction "K_1") (pintype "passive"))
      (node (ref "R1") (pin "2") (pinfunction "2_2") (pintype "passive"))
    )
    (net (code "37") (name "Net-(D3-K)") (class "Default")
      (node (ref "D3") (pin "1") (pinfunction "K_1") (pintype "passive"))
      (node (ref "R5") (pin "1") (pinfunction "1_1") (pintype "passive"))
    )
    (net (code "38") (name "Net-(D4-K)") (class "Default")
      (node (ref "D4") (pin "1") (pinfunction "K_1") (pintype "passive"))
      (node (ref "R20") (pin "1") (pinfunction "1_1") (pintype "passive"))
    )
    (net (code "39") (name "Net-(IC1-+5V-Pad3)") (class "Default")
      (node (ref "IC1") (pin "3") (pinfunction "+5V_3") (pintype "passive"))
      (node (ref "JP7") (pin "1") (pinfunction "1_1") (pintype "passive"))
      (node (ref "P2") (pin "1") (pinfunction "1_1") (pintype "passive"))
    )
    (net (code "40") (name "Net-(IC1-RX)") (class "Default")
      (node (ref "IC1") (pin "4") (pinfunction "RX_4") (pintype "passive"))
      (node (ref "JP8") (pin "2") (pinfunction "2_2") (pintype "passive"))
    )
    (net (code "41") (name "Net-(IC1-TX)") (class "Default")
      (node (ref "IC1") (pin "5") (pinfunction "TX_5") (pintype "passive"))
      (node (ref "JP9") (pin "2") (pinfunction "2_2") (pintype "passive"))
    )
    (net (code "42") (name "Net-(IC1-VIN)") (class "Default")
      (node (ref "IC1") (pin "8") (pinfunction "VIN_8") (pintype "passive"))
      (node (ref "P3") (pin "1") (pinfunction "1_1") (pintype "passive"))
    )
    (net (code "43") (name "Net-(IC1-VOUT)") (class "Default")
      (node (ref "IC1") (pin "10") (pinfunction "VOUT_10") (pintype "passive"))
      (node (ref "P1") (pin "1") (pinfunction "1_1") (pintype "passive"))
    )
    (net (code "44") (name "Net-(JP8-Pad1)") (class "Default")
      (node (ref "JP8") (pin "1") (pinfunction "1_1") (pintype "passive"))
      (node (ref "P2") (pin "2") (pinfunction "2_2") (pintype "passive"))
    )
    (net (code "45") (name "Net-(JP9-Pad1)") (class "Default")
      (node (ref "JP9") (pin "1") (pinfunction "1_1") (pintype "passive"))
      (node (ref "P2") (pin "3") (pinfunction "3_3") (pintype "passive"))
    )
    (net (code "46") (name "Net-(RF1-GPIO_0)") (class "Default")
      (node (ref "RF1") (pin "4") (pinfunction "TX_ANT_4") (pintype "passive"))
      (node (ref "RF1") (pin "6") (pinfunction "GPIO_0_6") (pintype "bidirectional"))
    )
    (net (code "47") (name "Net-(RF1-GPIO_1)") (class "Default")
      (node (ref "RF1") (pin "3") (pinfunction "RX_ANT_3") (pintype "passive"))
      (node (ref "RF1") (pin "7") (pinfunction "GPIO_1_7") (pintype "bidirectional"))
    )
    (net (code "48") (name "Net-(RF1-NIRQ)") (class "Default")
      (node (ref "R19") (pin "1") (pinfunction "1_1") (pintype "passive"))
      (node (ref "RF1") (pin "14") (pinfunction "NIRQ_14") (pintype "output"))
      (node (ref "U4") (pin "54") (pinfunction "PD2_-_Modem_IRQ_54") (pintype "bidirectional"))
    )
    (net (code "49") (name "Net-(RF1-NSEL)") (class "Default")
      (node (ref "R18") (pin "2") (pinfunction "2_2") (pintype "passive"))
      (node (ref "RF1") (pin "13") (pinfunction "NSEL_13") (pintype "input"))
      (node (ref "U4") (pin "50") (pinfunction "PA15_-_SPI3_NSS_50") (pintype "bidirectional"))
    )
    (net (code "50") (name "Net-(RF1-SCK)") (class "Default")
      (node (ref "RF1") (pin "12") (pinfunction "SCK_12") (pintype "input"))
      (node (ref "U4") (pin "51") (pinfunction "PC10_-_SPI3_SCK_51") (pintype "bidirectional"))
      (node (ref "U8") (pin "6") (pinfunction "SCK_6") (pintype "input"))
    )
    (net (code "51") (name "Net-(RF1-SDI)") (class "Default")
      (node (ref "RF1") (pin "11") (pinfunction "SDI_11") (pintype "input"))
      (node (ref "U4") (pin "53") (pinfunction "PC12_-_SPI3_MOSI_53") (pintype "bidirectional"))
      (node (ref "U8") (pin "5") (pinfunction "SI_5") (pintype "input"))
    )
    (net (code "52") (name "Net-(RF1-SDO)") (class "Default")
      (node (ref "RF1") (pin "10") (pinfunction "SDO_10") (pintype "output"))
      (node (ref "U4") (pin "52") (pinfunction "PC11_-_SPI3_MISO_52") (pintype "bidirectional"))
      (node (ref "U8") (pin "2") (pinfunction "SO_2") (pintype "output"))
    )
    (net (code "53") (name "Net-(RF1-VCC)") (class "Default")
      (node (ref "C30") (pin "1") (pinfunction "1_1") (pintype "passive"))
      (node (ref "C31") (pin "1") (pinfunction "1_1") (pintype "passive"))
      (node (ref "RF1") (pin "5") (pinfunction "VCC_5") (pintype "power_in"))
      (node (ref "U9") (pin "5") (pinfunction "VOUT_5") (pintype "power_in"))
    )
    (net (code "54") (name "Net-(U1-BYPASS)") (class "Default")
      (node (ref "C8") (pin "1") (pinfunction "1_1") (pintype "passive"))
      (node (ref "U1") (pin "4") (pinfunction "BYPASS_4") (pintype "passive"))
    )
    (net (code "55") (name "Net-(U2-BYPASS)") (class "Default")
      (node (ref "C9") (pin "1") (pinfunction "1_1") (pintype "passive"))
      (node (ref "U2") (pin "4") (pinfunction "BYPASS_4") (pintype "passive"))
    )
    (net (code "56") (name "Net-(U3-AD0{slash}SDO)") (class "Default")
      (node (ref "U3") (pin "9") (pinfunction "AD0/SDO_9") (pintype "input"))
      (node (ref "U4") (pin "22") (pinfunction "PA6_-_SPI1_MISO_22") (pintype "bidirectional"))
    )
    (net (code "57") (name "Net-(U3-CPOUT)") (class "Default")
      (node (ref "C12") (pin "2") (pinfunction "2_2") (pintype "passive"))
      (node (ref "U3") (pin "20") (pinfunction "CPOUT_20") (pintype "passive"))
    )
    (net (code "58") (name "Net-(U3-INT)") (class "Default")
      (node (ref "U3") (pin "12") (pinfunction "INT_12") (pintype "output"))
      (node (ref "U4") (pin "24") (pinfunction "PC4_-_Gyro_INT_24") (pintype "bidirectional"))
    )
    (net (code "59") (name "Net-(U3-REGOUT)") (class "Default")
      (node (ref "C13") (pin "1") (pinfunction "1_1") (pintype "passive"))
      (node (ref "U3") (pin "10") (pinfunction "REGOUT_10") (pintype "passive"))
    )
    (net (code "60") (name "Net-(U3-SCLK{slash}SCL)") (class "Default")
      (node (ref "U3") (pin "23") (pinfunction "SCLK/SCL_23") (pintype "input"))
      (node (ref "U4") (pin "21") (pinfunction "PA5_-_SPI1_SCK_21") (pintype "bidirectional"))
    )
    (net (code "61") (name "Net-(U3-SDI{slash}SDA)") (class "Default")
      (node (ref "U3") (pin "24") (pinfunction "SDI/SDA_24") (pintype "bidirectional"))
      (node (ref "U4") (pin "23") (pinfunction "PA7_-_SPI1_MOSI_23") (pintype "bidirectional"))
    )
    (net (code "62") (name "Net-(U3-VDD)") (class "Default")
      (node (ref "C10") (pin "2") (pinfunction "2_2") (pintype "passive"))
      (node (ref "C11") (pin "1") (pinfunction "1_1") (pintype "passive"))
      (node (ref "L1") (pin "2") (pinfunction "2_2") (pintype "passive"))
      (node (ref "U3") (pin "13") (pinfunction "VDD_13") (pintype "power_in"))
    )
    (net (code "63") (name "Net-(U3-{slash}CS)") (class "Default")
      (node (ref "R2") (pin "2") (pinfunction "2_2") (pintype "passive"))
      (node (ref "U3") (pin "8") (pinfunction "/CS_8") (pintype "passive"))
      (node (ref "U4") (pin "20") (pinfunction "PA4_-_SPI1_NSS_20") (pintype "bidirectional"))
    )
    (net (code "64") (name "Net-(U4-OSC_IN{slash}PD0)") (class "Default")
      (node (ref "U4") (pin "5") (pinfunction "OSC_IN/PD0_5") (pintype "input"))
      (node (ref "X1") (pin "1") (pinfunction "1_1") (pintype "passive"))
    )
    (net (code "65") (name "Net-(U4-OSC_OUT{slash}PD1)") (class "Default")
      (node (ref "U4") (pin "6") (pinfunction "OSC_OUT/PD1_6") (pintype "output"))
      (node (ref "X1") (pin "2") (pinfunction "2_2") (pintype "passive"))
    )
    (net (code "66") (name "Net-(U4-PB3_-_Flash_CS)") (class "Default")
      (node (ref "R15") (pin "2") (pinfunction "2_2") (pintype "passive"))
      (node (ref "U4") (pin "55") (pinfunction "PB3_-_Flash_CS_55") (pintype "bidirectional"))
      (node (ref "U8") (pin "1") (pinfunction "~{CS}_1") (pintype "input"))
    )
    (net (code "67") (name "Net-(U4-PB7_-_Mag_DRDY)") (class "Default")
      (node (ref "U4") (pin "59") (pinfunction "PB7_-_Mag_DRDY_59") (pintype "bidirectional"))
      (node (ref "U6") (pin "15") (pinfunction "DRDY_15") (pintype "power_in"))
    )
    (net (code "68") (name "Net-(U4-PB8_-_I2C1_SCL)") (class "Default")
      (node (ref "R17") (pin "2") (pinfunction "2_2") (pintype "passive"))
      (node (ref "U4") (pin "61") (pinfunction "PB8_-_I2C1_SCL_61") (pintype "bidirectional"))
      (node (ref "U6") (pin "1") (pinfunction "SCL_1") (pintype "passive"))
      (node (ref "U7") (pin "8") (pinfunction "SCLK_8") (pintype "passive"))
    )
    (net (code "69") (name "Net-(U4-PB9_-_I2C1_SDA)") (class "Default")
      (node (ref "R16") (pin "2") (pinfunction "2_2") (pintype "passive"))
      (node (ref "U4") (pin "62") (pinfunction "PB9_-_I2C1_SDA_62") (pintype "bidirectional"))
      (node (ref "U6") (pin "16") (pinfunction "SDA_16") (pintype "passive"))
      (node (ref "U7") (pin "7") (pinfunction "SDA_7") (pintype "passive"))
    )
    (net (code "70") (name "Net-(U4-PB10-I2C2_SCL)") (class "Default")
      (node (ref "CONN1") (pin "3") (pinfunction "3_3") (pintype "passive"))
      (node (ref "R4") (pin "1") (pinfunction "1_1") (pintype "passive"))
      (node (ref "U4") (pin "29") (pinfunction "PB10-I2C2_SCL_29") (pintype "bidirectional"))
    )
    (net (code "71") (name "Net-(U4-PB11-I2C2_SDA)") (class "Default")
      (node (ref "CONN1") (pin "4") (pinfunction "4_4") (pintype "passive"))
      (node (ref "R3") (pin "1") (pinfunction "1_1") (pintype "passive"))
      (node (ref "U4") (pin "30") (pinfunction "PB11-I2C2_SDA_30") (pintype "bidirectional"))
    )
    (net (code "72") (name "Net-(U4-PC3_-_Frequency)") (class "Default")
      (node (ref "R22") (pin "2") (pinfunction "2_2") (pintype "passive"))
      (node (ref "U4") (pin "11") (pinfunction "PC3_-_Frequency_11") (pintype "bidirectional"))
    )
    (net (code "73") (name "Net-(U4-VCP_1)") (class "Default")
      (node (ref "C14") (pin "2") (pinfunction "2_2") (pintype "passive"))
      (node (ref "U4") (pin "31") (pinfunction "VCP_1_31") (pintype "power_in"))
    )
    (net (code "74") (name "Net-(U4-VCP_2)") (class "Default")
      (node (ref "C25") (pin "2") (pinfunction "2_2") (pintype "passive"))
      (node (ref "U4") (pin "47") (pinfunction "VCP_2_47") (pintype "power_in"))
    )
    (net (code "75") (name "Net-(U6-C1)") (class "Default")
      (node (ref "C28") (pin "1") (pinfunction "1_1") (pintype "passive"))
      (node (ref "U6") (pin "10") (pinfunction "C1_10") (pintype "passive"))
    )
    (net (code "76") (name "Net-(U6-SETC)") (class "Default")
      (node (ref "C26") (pin "1") (pinfunction "1_1") (pintype "passive"))
      (node (ref "U6") (pin "12") (pinfunction "SETC_12") (pintype "power_in"))
    )
    (net (code "77") (name "Net-(U6-SETP)") (class "Default")
      (node (ref "C26") (pin "2") (pinfunction "2_2") (pintype "passive"))
      (node (ref "U6") (pin "8") (pinfunction "SETP_8") (pintype "passive"))
    )
    (net (code "78") (name "Net-(U7-PS)") (class "Default")
      (node (ref "C29") (pin "1") (pinfunction "1_1") (pintype "passive"))
      (node (ref "L3") (pin "1") (pinfunction "1_1") (pintype "passive"))
      (node (ref "U7") (pin "1") (pinfunction "VDD_1") (pintype "power_in"))
      (node (ref "U7") (pin "2") (pinfunction "PS_2") (pintype "passive"))
    )
    (net (code "79") (name "Net-(U9-BYPASS)") (class "Default")
      (node (ref "C34") (pin "1") (pinfunction "1_1") (pintype "passive"))
      (node (ref "U9") (pin "4") (pinfunction "BYPASS_4") (pintype "passive"))
    )
    (net (code "80") (name "TO_REGS") (class "Default")
      (node (ref "C2") (pin "1") (pinfunction "1_1") (pintype "passive"))
      (node (ref "C33") (pin "2") (pinfunction "2_2") (pintype "passive"))
      (node (ref "C35") (pin "1") (pinfunction "1_1") (pintype "passive"))
      (node (ref "C36") (pin "1") (pinfunction "1_1") (pintype "passive"))
      (node (ref "C5") (pin "1") (pinfunction "1_1") (pintype "passive"))
      (node (ref "C6") (pin "1") (pinfunction "1_1") (pintype "passive"))
      (node (ref "JP7") (pin "2") (pinfunction "2_2") (pintype "passive"))
      (node (ref "L4") (pin "1") (pinfunction "1_1") (pintype "passive"))
      (node (ref "U1") (pin "1") (pinfunction "VIN_1") (pintype "power_in"))
      (node (ref "U1") (pin "3") (pinfunction "ON/OFF_3") (pintype "input"))
      (node (ref "U2") (pin "1") (pinfunction "VIN_1") (pintype "power_in"))
      (node (ref "U2") (pin "3") (pinfunction "ON/OFF_3") (pintype "input"))
      (node (ref "U9") (pin "1") (pinfunction "VIN_1") (pintype "power_in"))
      (node (ref "U9") (pin "3") (pinfunction "ON/OFF_3") (pintype "input"))
    )
    (net (code "81") (name "VCC") (class "Default")
      (node (ref "C1") (pin "1") (pinfunction "1_1") (pintype "passive"))
      (node (ref "C15") (pin "1") (pinfunction "1_1") (pintype "passive"))
      (node (ref "C16") (pin "2") (pinfunction "2_2") (pintype "passive"))
      (node (ref "C17") (pin "2") (pinfunction "2_2") (pintype "passive"))
      (node (ref "C18") (pin "1") (pinfunction "1_1") (pintype "passive"))
      (node (ref "C20") (pin "2") (pinfunction "2_2") (pintype "passive"))
      (node (ref "C21") (pin "1") (pinfunction "1_1") (pintype "passive"))
      (node (ref "C22") (pin "2") (pinfunction "2_2") (pintype "passive"))
      (node (ref "C23") (pin "1") (pinfunction "1_1") (pintype "passive"))
      (node (ref "C24") (pin "2") (pinfunction "2_2") (pintype "passive"))
      (node (ref "C27") (pin "1") (pinfunction "1_1") (pintype "passive"))
      (node (ref "C3") (pin "1") (pinfunction "1_1") (pintype "passive"))
      (node (ref "D2") (pin "2") (pinfunction "A_2") (pintype "passive"))
      (node (ref "D3") (pin "2") (pinfunction "A_2") (pintype "passive"))
      (node (ref "D4") (pin "2") (pinfunction "A_2") (pintype "passive"))
      (node (ref "R15") (pin "1") (pinfunction "1_1") (pintype "passive"))
      (node (ref "R16") (pin "1") (pinfunction "1_1") (pintype "passive"))
      (node (ref "R17") (pin "1") (pinfunction "1_1") (pintype "passive"))
      (node (ref "R18") (pin "1") (pinfunction "1_1") (pintype "passive"))
      (node (ref "R19") (pin "2") (pinfunction "2_2") (pintype "passive"))
      (node (ref "R2") (pin "1") (pinfunction "1_1") (pintype "passive"))
      (node (ref "R22") (pin "1") (pinfunction "1_1") (pintype "passive"))
      (node (ref "R3") (pin "2") (pinfunction "2_2") (pintype "passive"))
      (node (ref "R4") (pin "2") (pinfunction "2_2") (pintype "passive"))
      (node (ref "R8") (pin "2") (pinfunction "2_2") (pintype "passive"))
      (node (ref "U1") (pin "5") (pinfunction "VOUT_5") (pintype "power_in"))
      (node (ref "U4") (pin "1") (pinfunction "VBAT_1") (pintype "power_in"))
      (node (ref "U4") (pin "13") (pinfunction "VDDA_13") (pintype "power_in"))
      (node (ref "U4") (pin "19") (pinfunction "VDD_4_19") (pintype "power_in"))
      (node (ref "U4") (pin "32") (pinfunction "VDD_1_32") (pintype "power_in"))
      (node (ref "U4") (pin "48") (pinfunction "VDD_2_48") (pintype "power_in"))
      (node (ref "U4") (pin "64") (pinfunction "VDD_3_64") (pintype "power_in"))
      (node (ref "U6") (pin "13") (pinfunction "VddIO_13") (pintype "passive"))
      (node (ref "U6") (pin "2") (pinfunction "Vdd_2") (pintype "power_in"))
      (node (ref "U6") (pin "4") (pinfunction "S1_4") (pintype "passive"))
      (node (ref "U8") (pin "3") (pinfunction "~{WP}_3") (pintype "input"))
      (node (ref "U8") (pin "7") (pinfunction "~{HOLD}_7") (pintype "input"))
      (node (ref "U8") (pin "8") (pinfunction "VCC_8") (pintype "power_in"))
    )
    (net (code "82") (name "VCC_ANA") (class "Default")
      (node (ref "C4") (pin "1") (pinfunction "1_1") (pintype "passive"))
      (node (ref "C7") (pin "1") (pinfunction "1_1") (pintype "passive"))
      (node (ref "L1") (pin "1") (pinfunction "1_1") (pintype "passive"))
      (node (ref "L3") (pin "2") (pinfunction "2_2") (pintype "passive"))
      (node (ref "U2") (pin "5") (pinfunction "VOUT_5") (pintype "power_in"))
    )
    (net (code "83") (name "VCC_UNREG") (class "Default")
      (node (ref "CONN4") (pin "2") (pinfunction "2_2") (pintype "passive"))
      (node (ref "CONN5") (pin "1") (pinfunction "VBUS_1") (pintype "passive"))
      (node (ref "JP1") (pin "2") (pinfunction "+_2") (pintype "passive"))
      (node (ref "JP2") (pin "2") (pinfunction "+_2") (pintype "passive"))
      (node (ref "JP3") (pin "2") (pinfunction "+_2") (pintype "passive"))
      (node (ref "JP4") (pin "2") (pinfunction "+_2") (pintype "passive"))
      (node (ref "JP5") (pin "2") (pinfunction "+_2") (pintype "passive"))
      (node (ref "JP6") (pin "2") (pinfunction "+_2") (pintype "passive"))
      (node (ref "L4") (pin "2") (pinfunction "2_2") (pintype "passive"))
      (node (ref "R12") (pin "1") (pinfunction "1_1") (pintype "passive"))
    )
    (net (code "84") (name "unconnected-(CONN1-Pad2)") (class "Default")
      (node (ref "CONN1") (pin "2") (pinfunction "2_2") (pintype "passive"))
    )
    (net (code "85") (name "unconnected-(CONN3-Pad1)") (class "Default")
      (node (ref "CONN3") (pin "1") (pinfunction "1_1") (pintype "passive"))
    )
    (net (code "86") (name "unconnected-(CONN3-Pad2)") (class "Default")
      (node (ref "CONN3") (pin "2") (pinfunction "2_2") (pintype "passive"))
    )
    (net (code "87") (name "unconnected-(CONN5-ID-Pad4)") (class "Default")
      (node (ref "CONN5") (pin "4") (pinfunction "ID_4") (pintype "passive"))
    )
    (net (code "88") (name "unconnected-(CONN6-Pad2)") (class "Default")
      (node (ref "CONN6") (pin "2") (pinfunction "2_2") (pintype "passive"))
    )
    (net (code "89") (name "unconnected-(IC1-+5V-Pad17)") (class "Default")
      (node (ref "IC1") (pin "17") (pinfunction "+5V_17") (pintype "passive"))
    )
    (net (code "90") (name "unconnected-(IC1-BAT1-Pad15)") (class "Default")
      (node (ref "IC1") (pin "15") (pinfunction "BAT1_15") (pintype "passive"))
    )
    (net (code "91") (name "unconnected-(IC1-BAT2-Pad14)") (class "Default")
      (node (ref "IC1") (pin "14") (pinfunction "BAT2_14") (pintype "passive"))
    )
    (net (code "92") (name "unconnected-(IC1-CURR-Pad12)") (class "Default")
      (node (ref "IC1") (pin "12") (pinfunction "CURR_12") (pintype "passive"))
    )
    (net (code "93") (name "unconnected-(IC1-DTR-Pad6)") (class "Default")
      (node (ref "IC1") (pin "6") (pinfunction "DTR_6") (pintype "passive"))
    )
    (net (code "94") (name "unconnected-(IC1-RSSI-Pad13)") (class "Default")
      (node (ref "IC1") (pin "13") (pinfunction "RSSI_13") (pintype "passive"))
    )
    (net (code "95") (name "unconnected-(J1-GND-Pad2)") (class "Default")
      (node (ref "J1") (pin "2") (pinfunction "GND_2") (pintype "power_in"))
    )
    (net (code "96") (name "unconnected-(J1-GND-Pad3)") (class "Default")
      (node (ref "J1") (pin "3") (pinfunction "GND_3") (pintype "power_in"))
    )
    (net (code "97") (name "unconnected-(J1-GND-Pad4)") (class "Default")
      (node (ref "J1") (pin "4") (pinfunction "GND_4") (pintype "power_in"))
    )
    (net (code "98") (name "unconnected-(J1-GND-Pad5)") (class "Default")
      (node (ref "J1") (pin "5") (pinfunction "GND_5") (pintype "power_in"))
    )
    (net (code "99") (name "unconnected-(J1-Signal-Pad1)") (class "Default")
      (node (ref "J1") (pin "1") (pinfunction "Signal_1") (pintype "input"))
    )
    (net (code "100") (name "unconnected-(RF1-GPIO_2-Pad8)") (class "Default")
      (node (ref "RF1") (pin "8") (pinfunction "GPIO_2_8") (pintype "bidirectional"))
    )
    (net (code "101") (name "unconnected-(RF1-N.C-Pad1)") (class "Default")
      (node (ref "RF1") (pin "1") (pinfunction "N.C_1") (pintype "tri_state"))
    )
    (net (code "102") (name "unconnected-(RF1-N.C-Pad4)") (class "Default")
      (node (ref "RF1") (pin "4") (pinfunction "N.C_4") (pintype "tri_state"))
    )
    (net (code "103") (name "unconnected-(RF1-N.C-Pad8)") (class "Default")
      (node (ref "RF1") (pin "8") (pinfunction "N.C_8") (pintype "tri_state"))
    )
    (net (code "104") (name "unconnected-(RF1-N.C-Pad9)") (class "Default")
      (node (ref "RF1") (pin "9") (pinfunction "N.C_9") (pintype "tri_state"))
    )
    (net (code "105") (name "unconnected-(RF1-N.C-Pad14)") (class "Default")
      (node (ref "RF1") (pin "14") (pinfunction "N.C_14") (pintype "tri_state"))
    )
    (net (code "106") (name "unconnected-(U3-AUX_CL-Pad7)") (class "Default")
      (node (ref "U3") (pin "7") (pinfunction "AUX_CL_7") (pintype "bidirectional"))
    )
    (net (code "107") (name "unconnected-(U3-AUX_DA-Pad6)") (class "Default")
      (node (ref "U3") (pin "6") (pinfunction "AUX_DA_6") (pintype "bidirectional"))
    )
    (net (code "108") (name "unconnected-(U3-CLKOUT-Pad22)") (class "Default")
      (node (ref "U3") (pin "22") (pinfunction "CLKOUT_22") (pintype "output"))
    )
    (net (code "109") (name "unconnected-(U3-NC-Pad2)") (class "Default")
      (node (ref "U3") (pin "2") (pinfunction "NC_2") (pintype "tri_state"))
    )
    (net (code "110") (name "unconnected-(U3-NC-Pad3)") (class "Default")
      (node (ref "U3") (pin "3") (pinfunction "NC_3") (pintype "tri_state"))
    )
    (net (code "111") (name "unconnected-(U3-NC-Pad4)") (class "Default")
      (node (ref "U3") (pin "4") (pinfunction "NC_4") (pintype "tri_state"))
    )
    (net (code "112") (name "unconnected-(U3-NC-Pad5)") (class "Default")
      (node (ref "U3") (pin "5") (pinfunction "NC_5") (pintype "tri_state"))
    )
    (net (code "113") (name "unconnected-(U3-NC-Pad14)") (class "Default")
      (node (ref "U3") (pin "14") (pinfunction "NC_14") (pintype "bidirectional"))
    )
    (net (code "114") (name "unconnected-(U3-NC-Pad15)") (class "Default")
      (node (ref "U3") (pin "15") (pinfunction "NC_15") (pintype "tri_state"))
    )
    (net (code "115") (name "unconnected-(U3-NC-Pad16)") (class "Default")
      (node (ref "U3") (pin "16") (pinfunction "NC_16") (pintype "tri_state"))
    )
    (net (code "116") (name "unconnected-(U3-NC-Pad17)") (class "Default")
      (node (ref "U3") (pin "17") (pinfunction "NC_17") (pintype "tri_state"))
    )
    (net (code "117") (name "unconnected-(U3-RESV-Pad19)") (class "Default")
      (node (ref "U3") (pin "19") (pinfunction "RESV_19") (pintype "passive"))
    )
    (net (code "118") (name "unconnected-(U3-RESV-Pad21)") (class "Default")
      (node (ref "U3") (pin "21") (pinfunction "RESV_21") (pintype "passive"))
    )
    (net (code "119") (name "unconnected-(U4-PB6_--Pad58)") (class "Default")
      (node (ref "U4") (pin "58") (pinfunction "PB6_-_58") (pintype "bidirectional"))
    )
    (net (code "120") (name "unconnected-(U4-PC13_-_RTC-Pad2)") (class "Default")
      (node (ref "U4") (pin "2") (pinfunction "PC13_-_RTC_2") (pintype "bidirectional"))
    )
    (net (code "121") (name "unconnected-(U4-PC14-OSC32_IN-Pad3)") (class "Default")
      (node (ref "U4") (pin "3") (pinfunction "PC14-OSC32_IN_3") (pintype "bidirectional"))
    )
    (net (code "122") (name "unconnected-(U4-PC15-OSC32_OUT-Pad4)") (class "Default")
      (node (ref "U4") (pin "4") (pinfunction "PC15-OSC32_OUT_4") (pintype "bidirectional"))
    )
    (net (code "123") (name "unconnected-(U6-NC-Pad3)") (class "Default")
      (node (ref "U6") (pin "3") (pinfunction "NC_3") (pintype "passive"))
    )
    (net (code "124") (name "unconnected-(U6-NC-Pad5)") (class "Default")
      (node (ref "U6") (pin "5") (pinfunction "NC_5") (pintype "passive"))
    )
    (net (code "125") (name "unconnected-(U6-NC-Pad6)") (class "Default")
      (node (ref "U6") (pin "6") (pinfunction "NC_6") (pintype "passive"))
    )
    (net (code "126") (name "unconnected-(U6-NC-Pad7)") (class "Default")
      (node (ref "U6") (pin "7") (pinfunction "NC_7") (pintype "passive"))
    )
    (net (code "127") (name "unconnected-(U6-NC-Pad8)") (class "Default")
      (node (ref "U6") (pin "8") (pinfunction "NC_8") (pintype "passive"))
    )
    (net (code "128") (name "unconnected-(U6-NC-Pad14)") (class "Default")
      (node (ref "U6") (pin "14") (pinfunction "NC_14") (pintype "passive"))
    )
    (net (code "129") (name "unconnected-(U7-CSB-Pad5)") (class "Default")
      (node (ref "U7") (pin "5") (pinfunction "CSB_5") (pintype "passive"))
    )
    (net (code "130") (name "unconnected-(U7-SDO-Pad6)") (class "Default")
      (node (ref "U7") (pin "6") (pinfunction "SDO_6") (pintype "passive"))
    )
  )
)
